# encoder_rs485.net
KiCad netlist of a schematic drawn in EAGLE
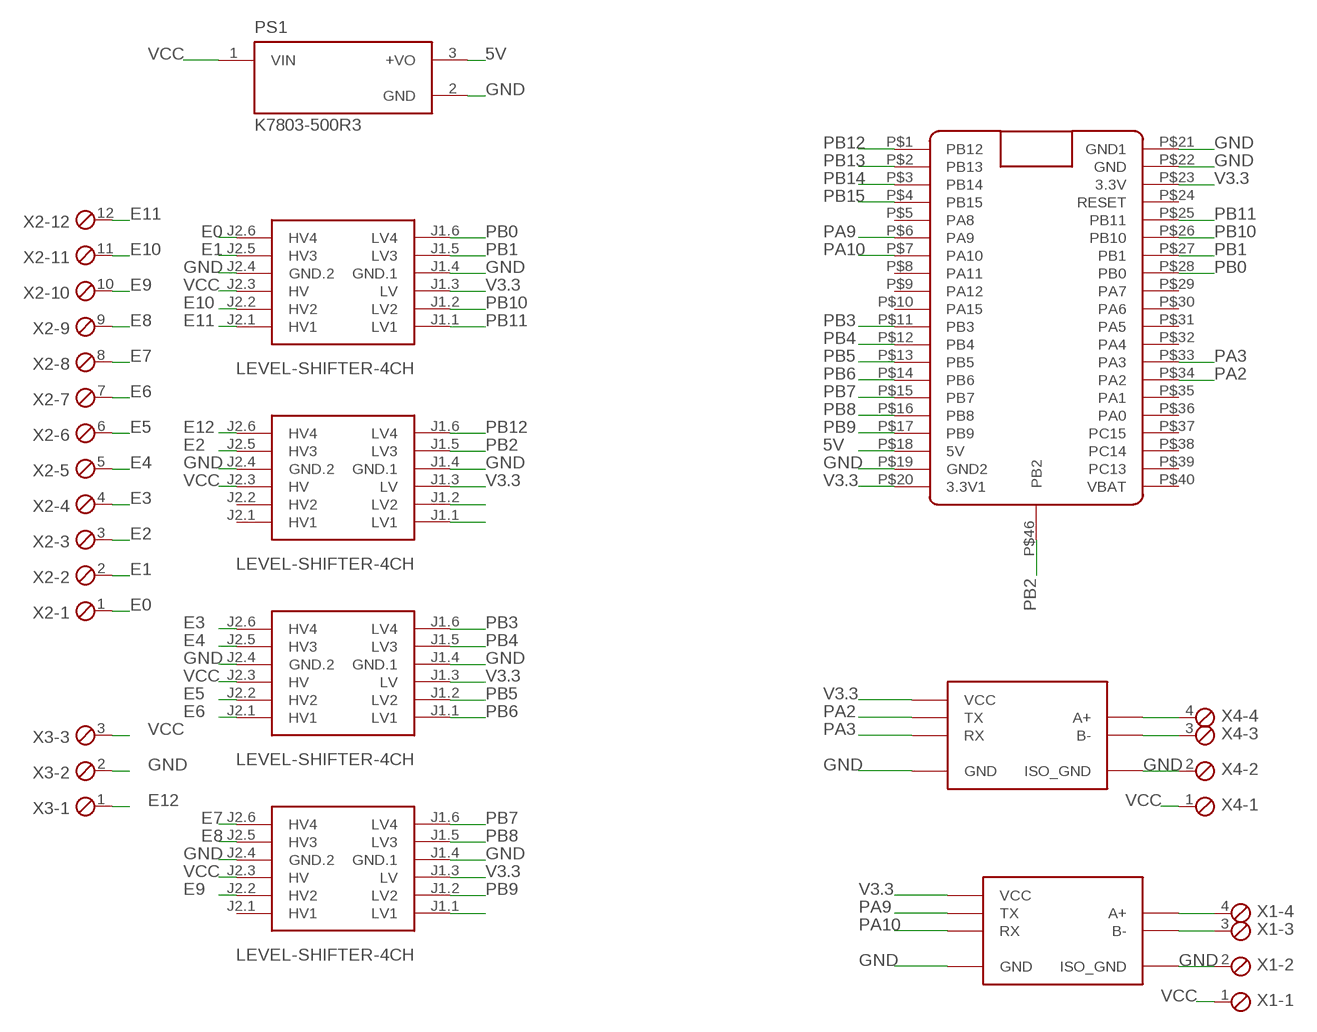
[diagram p0: schematic, sheet 1]

(export (version "E")
  (design (tool "Eeschema 10.0.6"))
  (components
    (comp (ref "PS1")
      (value "K7803-500R3")
      (footprint "eagle-import:CONV_K7803-500R3")
      (fields (field (name "MF") "Mornsun America, LLC"))
      (libsource (lib "eagle-import") (part "K7803-500R3"))
    )
    (comp (ref "U$1")
      (value "LIMNOTECH_SMC_RS485")
      (footprint "eagle-import:LIMNOTECH_SMC_RS485")
      (libsource (lib "eagle-import") (part "LIMNOTECH_SMC_RS485"))
    )
    (comp (ref "U$2")
      (value "LEVEL-SHIFTER-4CH")
      (footprint "eagle-import:LEVEL-SHIFTER-4CH")
      (libsource (lib "eagle-import") (part "LEVEL-SHIFTER-4CH"))
    )
    (comp (ref "U$3")
      (value "LEVEL-SHIFTER-4CH")
      (footprint "eagle-import:LEVEL-SHIFTER-4CH")
      (libsource (lib "eagle-import") (part "LEVEL-SHIFTER-4CH"))
    )
    (comp (ref "U$4")
      (value "LEVEL-SHIFTER-4CH")
      (footprint "eagle-import:LEVEL-SHIFTER-4CH")
      (libsource (lib "eagle-import") (part "LEVEL-SHIFTER-4CH"))
    )
    (comp (ref "U$5")
      (value "LEVEL-SHIFTER-4CH")
      (footprint "eagle-import:LEVEL-SHIFTER-4CH")
      (libsource (lib "eagle-import") (part "LEVEL-SHIFTER-4CH"))
    )
    (comp (ref "U$6")
      (value "BLUE_PILLADVANCED")
      (footprint "eagle-import:BLUE_PILL_ADV")
      (libsource (lib "eagle-import") (part "BLUE_PILLADVANCED"))
    )
    (comp (ref "U$7")
      (value "LIMNOTECH_SMC_RS485")
      (footprint "eagle-import:LIMNOTECH_SMC_RS485")
      (libsource (lib "eagle-import") (part "LIMNOTECH_SMC_RS485"))
    )
    (comp (ref "X1")
      (value "MKDS1/4-3,81")
      (footprint "eagle-import:4POL381")
      (libsource (lib "eagle-import") (part "MKDS1/4-3,81"))
    )
    (comp (ref "X2")
      (value "MKDS1/12-3,81")
      (footprint "eagle-import:12POL381")
      (libsource (lib "eagle-import") (part "MKDS1/12-3,81"))
    )
    (comp (ref "X3")
      (value "MKDS1/3-3,81")
      (footprint "eagle-import:3POL381")
      (libsource (lib "eagle-import") (part "MKDS1/3-3,81"))
    )
    (comp (ref "X4")
      (value "MKDS1/4-3,81")
      (footprint "eagle-import:4POL381")
      (libsource (lib "eagle-import") (part "MKDS1/4-3,81"))
    )
  )
  (nets
    (net (code "1") (name "/5V") (class "Default")
      (node (ref "PS1") (pin "3") (pinfunction "+VO_3") (pintype "output"))
      (node (ref "U$6") (pin "P$18") (pinfunction "5V_P$18") (pintype "bidirectional"))
    )
    (net (code "2") (name "/E0") (class "Default")
      (node (ref "U$2") (pin "J2.6") (pinfunction "HV4_J2.6") (pintype "bidirectional"))
      (node (ref "X2") (pin "1") (pinfunction "1_1") (pintype "passive"))
    )
    (net (code "3") (name "/E1") (class "Default")
      (node (ref "U$2") (pin "J2.5") (pinfunction "HV3_J2.5") (pintype "bidirectional"))
      (node (ref "X2") (pin "2") (pinfunction "1_2") (pintype "passive"))
    )
    (net (code "4") (name "/E2") (class "Default")
      (node (ref "U$3") (pin "J2.5") (pinfunction "HV3_J2.5") (pintype "bidirectional"))
      (node (ref "X2") (pin "3") (pinfunction "1_3") (pintype "passive"))
    )
    (net (code "5") (name "/E3") (class "Default")
      (node (ref "U$4") (pin "J2.6") (pinfunction "HV4_J2.6") (pintype "bidirectional"))
      (node (ref "X2") (pin "4") (pinfunction "1_4") (pintype "passive"))
    )
    (net (code "6") (name "/E4") (class "Default")
      (node (ref "U$4") (pin "J2.5") (pinfunction "HV3_J2.5") (pintype "bidirectional"))
      (node (ref "X2") (pin "5") (pinfunction "1_5") (pintype "passive"))
    )
    (net (code "7") (name "/E5") (class "Default")
      (node (ref "U$4") (pin "J2.2") (pinfunction "HV2_J2.2") (pintype "bidirectional"))
      (node (ref "X2") (pin "6") (pinfunction "1_6") (pintype "passive"))
    )
    (net (code "8") (name "/E6") (class "Default")
      (node (ref "U$4") (pin "J2.1") (pinfunction "HV1_J2.1") (pintype "bidirectional"))
      (node (ref "X2") (pin "7") (pinfunction "1_7") (pintype "passive"))
    )
    (net (code "9") (name "/E7") (class "Default")
      (node (ref "U$5") (pin "J2.6") (pinfunction "HV4_J2.6") (pintype "bidirectional"))
      (node (ref "X2") (pin "8") (pinfunction "1_8") (pintype "passive"))
    )
    (net (code "10") (name "/E8") (class "Default")
      (node (ref "U$5") (pin "J2.5") (pinfunction "HV3_J2.5") (pintype "bidirectional"))
      (node (ref "X2") (pin "9") (pinfunction "1_9") (pintype "passive"))
    )
    (net (code "11") (name "/E9") (class "Default")
      (node (ref "U$5") (pin "J2.2") (pinfunction "HV2_J2.2") (pintype "bidirectional"))
      (node (ref "X2") (pin "10") (pinfunction "1_10") (pintype "passive"))
    )
    (net (code "12") (name "/E10") (class "Default")
      (node (ref "U$2") (pin "J2.2") (pinfunction "HV2_J2.2") (pintype "bidirectional"))
      (node (ref "X2") (pin "11") (pinfunction "1_11") (pintype "passive"))
    )
    (net (code "13") (name "/E11") (class "Default")
      (node (ref "U$2") (pin "J2.1") (pinfunction "HV1_J2.1") (pintype "bidirectional"))
      (node (ref "X2") (pin "12") (pinfunction "1_12") (pintype "passive"))
    )
    (net (code "14") (name "/E12") (class "Default")
      (node (ref "U$3") (pin "J2.6") (pinfunction "HV4_J2.6") (pintype "bidirectional"))
      (node (ref "X3") (pin "1") (pinfunction "1_1") (pintype "passive"))
    )
    (net (code "15") (name "/GND") (class "Default")
      (node (ref "PS1") (pin "2") (pinfunction "GND_2") (pintype "power_in"))
      (node (ref "U$1") (pin "GND") (pinfunction "GND_GND") (pintype "bidirectional"))
      (node (ref "U$1") (pin "GND_ISO") (pinfunction "ISO_GND_GND_ISO") (pintype "bidirectional"))
      (node (ref "U$2") (pin "J1.4") (pinfunction "GND.1_J1.4") (pintype "power_in"))
      (node (ref "U$2") (pin "J2.4") (pinfunction "GND.2_J2.4") (pintype "power_in"))
      (node (ref "U$3") (pin "J1.4") (pinfunction "GND.1_J1.4") (pintype "power_in"))
      (node (ref "U$3") (pin "J2.4") (pinfunction "GND.2_J2.4") (pintype "power_in"))
      (node (ref "U$4") (pin "J1.4") (pinfunction "GND.1_J1.4") (pintype "power_in"))
      (node (ref "U$4") (pin "J2.4") (pinfunction "GND.2_J2.4") (pintype "power_in"))
      (node (ref "U$5") (pin "J1.4") (pinfunction "GND.1_J1.4") (pintype "power_in"))
      (node (ref "U$5") (pin "J2.4") (pinfunction "GND.2_J2.4") (pintype "power_in"))
      (node (ref "U$6") (pin "P$19") (pinfunction "GND2_P$19") (pintype "bidirectional"))
      (node (ref "U$6") (pin "P$21") (pinfunction "GND1_P$21") (pintype "power_in"))
      (node (ref "U$6") (pin "P$22") (pinfunction "GND_P$22") (pintype "bidirectional"))
      (node (ref "U$7") (pin "GND") (pinfunction "GND_GND") (pintype "bidirectional"))
      (node (ref "U$7") (pin "GND_ISO") (pinfunction "ISO_GND_GND_ISO") (pintype "bidirectional"))
      (node (ref "X1") (pin "2") (pinfunction "1_2") (pintype "passive"))
      (node (ref "X3") (pin "2") (pinfunction "1_2") (pintype "passive"))
      (node (ref "X4") (pin "2") (pinfunction "1_2") (pintype "passive"))
    )
    (net (code "16") (name "/PA2") (class "Default")
      (node (ref "U$6") (pin "P$34") (pinfunction "PA2_P$34") (pintype "bidirectional"))
      (node (ref "U$7") (pin "TX") (pinfunction "TX_TX") (pintype "bidirectional"))
    )
    (net (code "17") (name "/PA3") (class "Default")
      (node (ref "U$6") (pin "P$33") (pinfunction "PA3_P$33") (pintype "bidirectional"))
      (node (ref "U$7") (pin "RX") (pinfunction "RX_RX") (pintype "bidirectional"))
    )
    (net (code "18") (name "/PA9") (class "Default")
      (node (ref "U$1") (pin "TX") (pinfunction "TX_TX") (pintype "bidirectional"))
      (node (ref "U$6") (pin "P$6") (pinfunction "PA9_P$6") (pintype "bidirectional"))
    )
    (net (code "19") (name "/PA10") (class "Default")
      (node (ref "U$1") (pin "RX") (pinfunction "RX_RX") (pintype "bidirectional"))
      (node (ref "U$6") (pin "P$7") (pinfunction "PA10_P$7") (pintype "bidirectional"))
    )
    (net (code "20") (name "/PB0") (class "Default")
      (node (ref "U$2") (pin "J1.6") (pinfunction "LV4_J1.6") (pintype "bidirectional"))
      (node (ref "U$6") (pin "P$28") (pinfunction "PB0_P$28") (pintype "bidirectional"))
    )
    (net (code "21") (name "/PB1") (class "Default")
      (node (ref "U$2") (pin "J1.5") (pinfunction "LV3_J1.5") (pintype "bidirectional"))
      (node (ref "U$6") (pin "P$27") (pinfunction "PB1_P$27") (pintype "bidirectional"))
    )
    (net (code "22") (name "/PB2") (class "Default")
      (node (ref "U$3") (pin "J1.5") (pinfunction "LV3_J1.5") (pintype "bidirectional"))
      (node (ref "U$6") (pin "P$46") (pinfunction "PB2_P$46") (pintype "bidirectional"))
    )
    (net (code "23") (name "/PB3") (class "Default")
      (node (ref "U$4") (pin "J1.6") (pinfunction "LV4_J1.6") (pintype "bidirectional"))
      (node (ref "U$6") (pin "P$11") (pinfunction "PB3_P$11") (pintype "bidirectional"))
    )
    (net (code "24") (name "/PB4") (class "Default")
      (node (ref "U$4") (pin "J1.5") (pinfunction "LV3_J1.5") (pintype "bidirectional"))
      (node (ref "U$6") (pin "P$12") (pinfunction "PB4_P$12") (pintype "bidirectional"))
    )
    (net (code "25") (name "/PB5") (class "Default")
      (node (ref "U$4") (pin "J1.2") (pinfunction "LV2_J1.2") (pintype "bidirectional"))
      (node (ref "U$6") (pin "P$13") (pinfunction "PB5_P$13") (pintype "bidirectional"))
    )
    (net (code "26") (name "/PB6") (class "Default")
      (node (ref "U$4") (pin "J1.1") (pinfunction "LV1_J1.1") (pintype "bidirectional"))
      (node (ref "U$6") (pin "P$14") (pinfunction "PB6_P$14") (pintype "bidirectional"))
    )
    (net (code "27") (name "/PB7") (class "Default")
      (node (ref "U$5") (pin "J1.6") (pinfunction "LV4_J1.6") (pintype "bidirectional"))
      (node (ref "U$6") (pin "P$15") (pinfunction "PB7_P$15") (pintype "bidirectional"))
    )
    (net (code "28") (name "/PB8") (class "Default")
      (node (ref "U$5") (pin "J1.5") (pinfunction "LV3_J1.5") (pintype "bidirectional"))
      (node (ref "U$6") (pin "P$16") (pinfunction "PB8_P$16") (pintype "bidirectional"))
    )
    (net (code "29") (name "/PB9") (class "Default")
      (node (ref "U$5") (pin "J1.2") (pinfunction "LV2_J1.2") (pintype "bidirectional"))
      (node (ref "U$6") (pin "P$17") (pinfunction "PB9_P$17") (pintype "bidirectional"))
    )
    (net (code "30") (name "/PB10") (class "Default")
      (node (ref "U$2") (pin "J1.2") (pinfunction "LV2_J1.2") (pintype "bidirectional"))
      (node (ref "U$6") (pin "P$26") (pinfunction "PB10_P$26") (pintype "bidirectional"))
    )
    (net (code "31") (name "/PB11") (class "Default")
      (node (ref "U$2") (pin "J1.1") (pinfunction "LV1_J1.1") (pintype "bidirectional"))
      (node (ref "U$6") (pin "P$25") (pinfunction "PB11_P$25") (pintype "bidirectional"))
    )
    (net (code "32") (name "/PB12") (class "Default")
      (node (ref "U$3") (pin "J1.6") (pinfunction "LV4_J1.6") (pintype "bidirectional"))
      (node (ref "U$6") (pin "P$1") (pinfunction "PB12_P$1") (pintype "bidirectional"))
    )
    (net (code "33") (name "/PB13") (class "Default")
      (node (ref "U$6") (pin "P$2") (pinfunction "PB13_P$2") (pintype "bidirectional"))
    )
    (net (code "34") (name "/PB14") (class "Default")
      (node (ref "U$6") (pin "P$3") (pinfunction "PB14_P$3") (pintype "bidirectional"))
    )
    (net (code "35") (name "/PB15") (class "Default")
      (node (ref "U$6") (pin "P$4") (pinfunction "PB15_P$4") (pintype "bidirectional"))
    )
    (net (code "36") (name "/V3.3") (class "Default")
      (node (ref "U$1") (pin "VCC") (pinfunction "VCC_VCC") (pintype "bidirectional"))
      (node (ref "U$2") (pin "J1.3") (pinfunction "LV_J1.3") (pintype "power_in"))
      (node (ref "U$3") (pin "J1.3") (pinfunction "LV_J1.3") (pintype "power_in"))
      (node (ref "U$4") (pin "J1.3") (pinfunction "LV_J1.3") (pintype "power_in"))
      (node (ref "U$5") (pin "J1.3") (pinfunction "LV_J1.3") (pintype "power_in"))
      (node (ref "U$6") (pin "P$20") (pinfunction "3.3V1_P$20") (pintype "bidirectional"))
      (node (ref "U$6") (pin "P$23") (pinfunction "3.3V_P$23") (pintype "bidirectional"))
      (node (ref "U$7") (pin "VCC") (pinfunction "VCC_VCC") (pintype "bidirectional"))
    )
    (net (code "37") (name "/VCC") (class "Default")
      (node (ref "PS1") (pin "1") (pinfunction "VIN_1") (pintype "input"))
      (node (ref "U$2") (pin "J2.3") (pinfunction "HV_J2.3") (pintype "power_in"))
      (node (ref "U$3") (pin "J2.3") (pinfunction "HV_J2.3") (pintype "power_in"))
      (node (ref "U$4") (pin "J2.3") (pinfunction "HV_J2.3") (pintype "power_in"))
      (node (ref "U$5") (pin "J2.3") (pinfunction "HV_J2.3") (pintype "power_in"))
      (node (ref "X1") (pin "1") (pinfunction "1_1") (pintype "passive"))
      (node (ref "X3") (pin "3") (pinfunction "1_3") (pintype "passive"))
      (node (ref "X4") (pin "1") (pinfunction "1_1") (pintype "passive"))
    )
    (net (code "38") (name "Net-(X1C-1)") (class "Default")
      (node (ref "U$1") (pin "B-") (pinfunction "B-_B-") (pintype "bidirectional"))
      (node (ref "X1") (pin "3") (pinfunction "1_3") (pintype "passive"))
    )
    (net (code "39") (name "Net-(X1D-1)") (class "Default")
      (node (ref "U$1") (pin "A+") (pinfunction "A+_A+") (pintype "bidirectional"))
      (node (ref "X1") (pin "4") (pinfunction "1_4") (pintype "passive"))
    )
    (net (code "40") (name "Net-(X4C-1)") (class "Default")
      (node (ref "U$7") (pin "B-") (pinfunction "B-_B-") (pintype "bidirectional"))
      (node (ref "X4") (pin "3") (pinfunction "1_3") (pintype "passive"))
    )
    (net (code "41") (name "Net-(X4D-1)") (class "Default")
      (node (ref "U$7") (pin "A+") (pinfunction "A+_A+") (pintype "bidirectional"))
      (node (ref "X4") (pin "4") (pinfunction "1_4") (pintype "passive"))
    )
    (net (code "42") (name "unconnected-(U$3-HV1-PadJ2.1)") (class "Default")
      (node (ref "U$3") (pin "J2.1") (pinfunction "HV1_J2.1") (pintype "bidirectional"))
    )
    (net (code "43") (name "unconnected-(U$3-HV2-PadJ2.2)") (class "Default")
      (node (ref "U$3") (pin "J2.2") (pinfunction "HV2_J2.2") (pintype "bidirectional"))
    )
    (net (code "44") (name "unconnected-(U$3-LV1-PadJ1.1)") (class "Default")
      (node (ref "U$3") (pin "J1.1") (pinfunction "LV1_J1.1") (pintype "bidirectional"))
    )
    (net (code "45") (name "unconnected-(U$3-LV2-PadJ1.2)") (class "Default")
      (node (ref "U$3") (pin "J1.2") (pinfunction "LV2_J1.2") (pintype "bidirectional"))
    )
    (net (code "46") (name "unconnected-(U$5-HV1-PadJ2.1)") (class "Default")
      (node (ref "U$5") (pin "J2.1") (pinfunction "HV1_J2.1") (pintype "bidirectional"))
    )
    (net (code "47") (name "unconnected-(U$5-LV1-PadJ1.1)") (class "Default")
      (node (ref "U$5") (pin "J1.1") (pinfunction "LV1_J1.1") (pintype "bidirectional"))
    )
    (net (code "48") (name "unconnected-(U$6-PA0-PadP$36)") (class "Default")
      (node (ref "U$6") (pin "P$36") (pinfunction "PA0_P$36") (pintype "bidirectional"))
    )
    (net (code "49") (name "unconnected-(U$6-PA1-PadP$35)") (class "Default")
      (node (ref "U$6") (pin "P$35") (pinfunction "PA1_P$35") (pintype "bidirectional"))
    )
    (net (code "50") (name "unconnected-(U$6-PA4-PadP$32)") (class "Default")
      (node (ref "U$6") (pin "P$32") (pinfunction "PA4_P$32") (pintype "bidirectional"))
    )
    (net (code "51") (name "unconnected-(U$6-PA5-PadP$31)") (class "Default")
      (node (ref "U$6") (pin "P$31") (pinfunction "PA5_P$31") (pintype "bidirectional"))
    )
    (net (code "52") (name "unconnected-(U$6-PA6-PadP$30)") (class "Default")
      (node (ref "U$6") (pin "P$30") (pinfunction "PA6_P$30") (pintype "bidirectional"))
    )
    (net (code "53") (name "unconnected-(U$6-PA7-PadP$29)") (class "Default")
      (node (ref "U$6") (pin "P$29") (pinfunction "PA7_P$29") (pintype "bidirectional"))
    )
    (net (code "54") (name "unconnected-(U$6-PA8-PadP$5)") (class "Default")
      (node (ref "U$6") (pin "P$5") (pinfunction "PA8_P$5") (pintype "bidirectional"))
    )
    (net (code "55") (name "unconnected-(U$6-PA11-PadP$8)") (class "Default")
      (node (ref "U$6") (pin "P$8") (pinfunction "PA11_P$8") (pintype "bidirectional"))
    )
    (net (code "56") (name "unconnected-(U$6-PA12-PadP$9)") (class "Default")
      (node (ref "U$6") (pin "P$9") (pinfunction "PA12_P$9") (pintype "bidirectional"))
    )
    (net (code "57") (name "unconnected-(U$6-PA15-PadP$10)") (class "Default")
      (node (ref "U$6") (pin "P$10") (pinfunction "PA15_P$10") (pintype "bidirectional"))
    )
    (net (code "58") (name "unconnected-(U$6-PC13-PadP$39)") (class "Default")
      (node (ref "U$6") (pin "P$39") (pinfunction "PC13_P$39") (pintype "bidirectional"))
    )
    (net (code "59") (name "unconnected-(U$6-PC14-PadP$38)") (class "Default")
      (node (ref "U$6") (pin "P$38") (pinfunction "PC14_P$38") (pintype "bidirectional"))
    )
    (net (code "60") (name "unconnected-(U$6-PC15-PadP$37)") (class "Default")
      (node (ref "U$6") (pin "P$37") (pinfunction "PC15_P$37") (pintype "bidirectional"))
    )
    (net (code "61") (name "unconnected-(U$6-RESET-PadP$24)") (class "Default")
      (node (ref "U$6") (pin "P$24") (pinfunction "RESET_P$24") (pintype "bidirectional"))
    )
    (net (code "62") (name "unconnected-(U$6-VBAT-PadP$40)") (class "Default")
      (node (ref "U$6") (pin "P$40") (pinfunction "VBAT_P$40") (pintype "bidirectional"))
    )
  )
)
